# micromouse.net
KiCad netlist of a schematic drawn in EAGLE
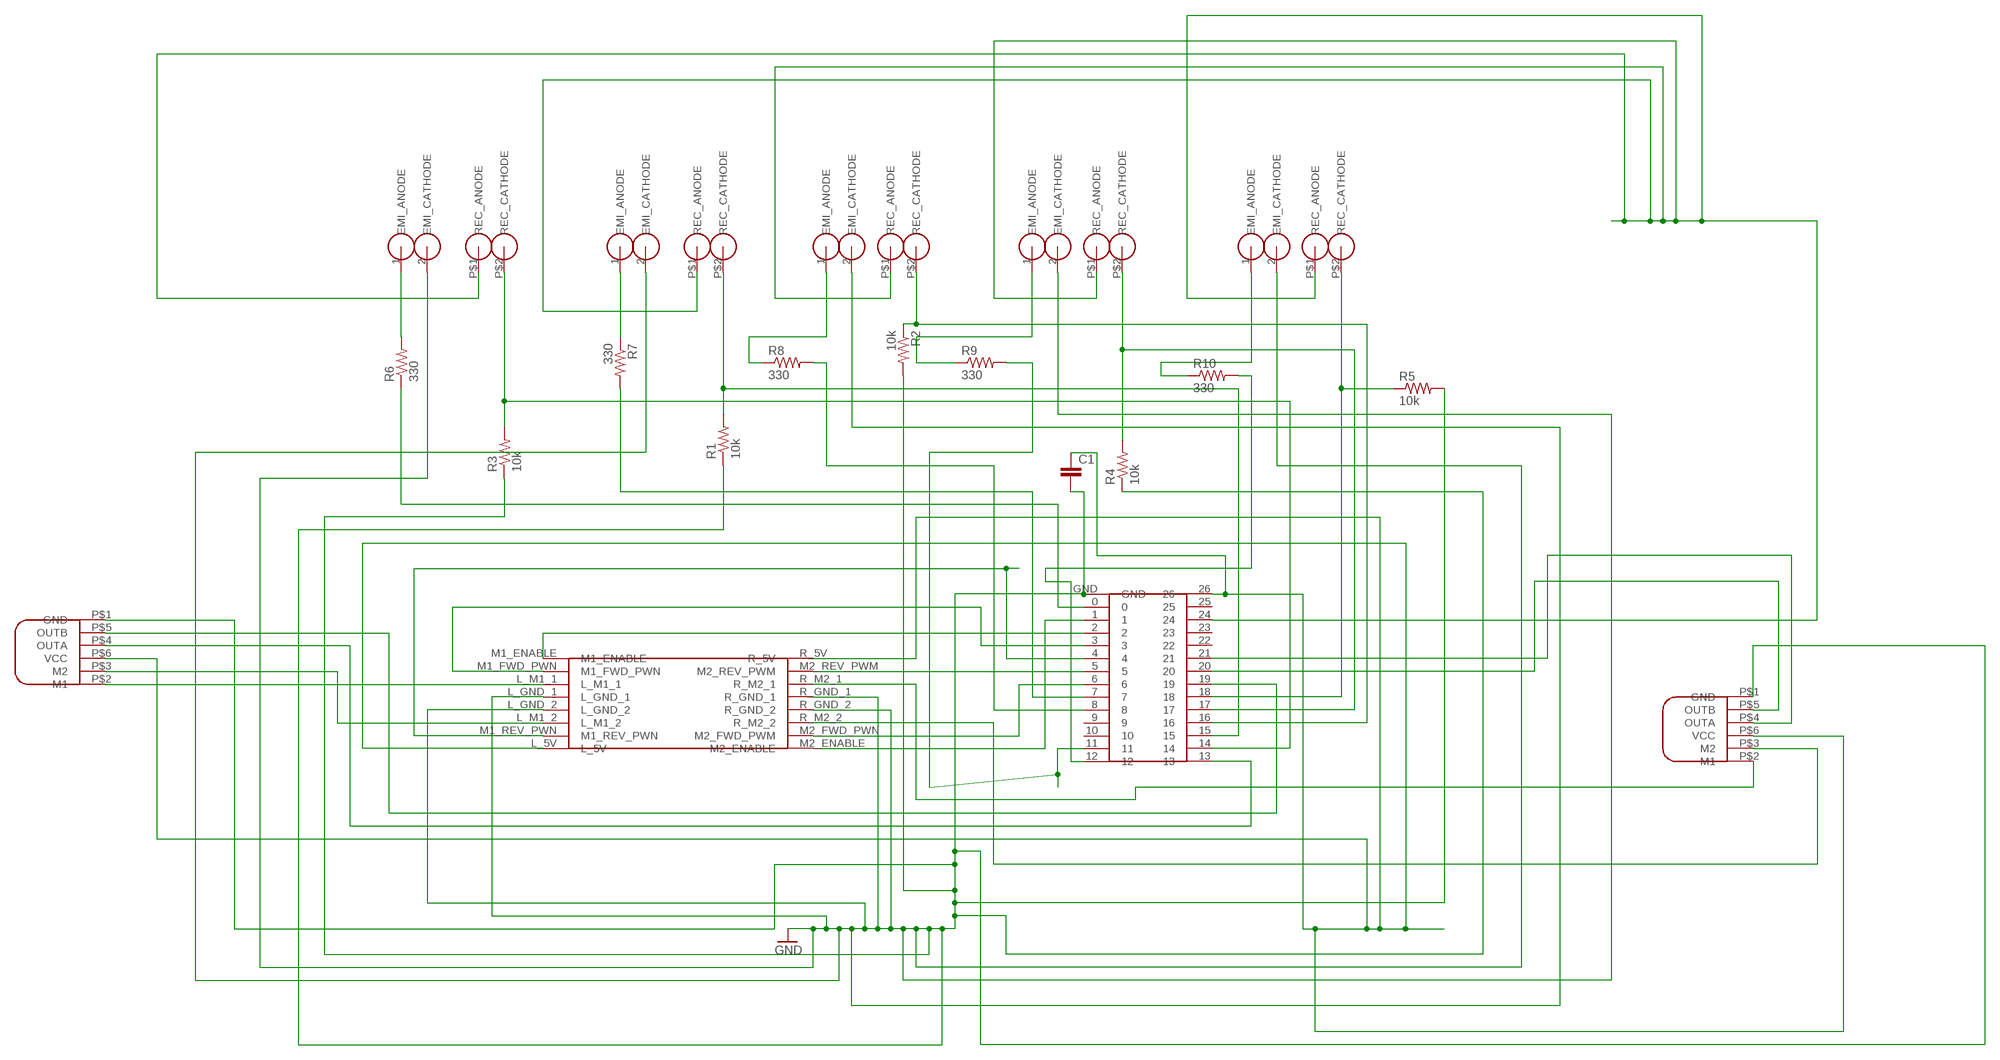
[diagram p0: schematic, sheet 1]

(export (version "E")
  (design (tool "Eeschema 10.0.6"))
  (components
    (comp (ref "C1")
      (value "C2,5-3")
      (footprint "eagle-import:C2.5-3")
      (libsource (lib "eagle-import") (part "C2,5-3"))
    )
    (comp (ref "R1")
      (value "10k")
      (footprint "eagle-import:0204_5")
      (libsource (lib "eagle-import") (part "R-US_0204/5"))
    )
    (comp (ref "R2")
      (value "10k")
      (footprint "eagle-import:0204_5")
      (libsource (lib "eagle-import") (part "R-US_0204/5"))
    )
    (comp (ref "R3")
      (value "10k")
      (footprint "eagle-import:0204_5")
      (libsource (lib "eagle-import") (part "R-US_0204/5"))
    )
    (comp (ref "R4")
      (value "10k")
      (footprint "eagle-import:0204_5")
      (libsource (lib "eagle-import") (part "R-US_0204/5"))
    )
    (comp (ref "R5")
      (value "10k")
      (footprint "eagle-import:0204_5")
      (libsource (lib "eagle-import") (part "R-US_0204/5"))
    )
    (comp (ref "R6")
      (value "330")
      (footprint "eagle-import:0204_5")
      (libsource (lib "eagle-import") (part "R-US_0204/5"))
    )
    (comp (ref "R7")
      (value "330")
      (footprint "eagle-import:0204_5")
      (libsource (lib "eagle-import") (part "R-US_0204/5"))
    )
    (comp (ref "R8")
      (value "330")
      (footprint "eagle-import:0204_5")
      (libsource (lib "eagle-import") (part "R-US_0204/5"))
    )
    (comp (ref "R9")
      (value "330")
      (footprint "eagle-import:0204_5")
      (libsource (lib "eagle-import") (part "R-US_0204/5"))
    )
    (comp (ref "R10")
      (value "330")
      (footprint "eagle-import:0204_5")
      (libsource (lib "eagle-import") (part "R-US_0204/5"))
    )
    (comp (ref "U$1")
      (value "TEENSY3.2")
      (footprint "eagle-import:TEENSY3.2")
      (libsource (lib "eagle-import") (part "TEENSY3.2"))
    )
    (comp (ref "U$2")
      (value "MOTOR_DRIVER")
      (footprint "eagle-import:MOTOR_DRIVER")
      (libsource (lib "eagle-import") (part "MOTOR_DRIVER"))
    )
    (comp (ref "U$3")
      (value "IR_RECIEVER")
      (footprint "eagle-import:IR_RECIEVER")
      (libsource (lib "eagle-import") (part "IR_RECIEVER"))
    )
    (comp (ref "U$4")
      (value "IR_RECIEVER")
      (footprint "eagle-import:IR_RECIEVER")
      (libsource (lib "eagle-import") (part "IR_RECIEVER"))
    )
    (comp (ref "U$5")
      (value "IR_RECIEVER")
      (footprint "eagle-import:IR_RECIEVER")
      (libsource (lib "eagle-import") (part "IR_RECIEVER"))
    )
    (comp (ref "U$6")
      (value "IR_RECIEVER")
      (footprint "eagle-import:IR_RECIEVER")
      (libsource (lib "eagle-import") (part "IR_RECIEVER"))
    )
    (comp (ref "U$7")
      (value "IR_RECIEVER")
      (footprint "eagle-import:IR_RECIEVER")
      (libsource (lib "eagle-import") (part "IR_RECIEVER"))
    )
    (comp (ref "U$8")
      (value "IR_EMITTER")
      (footprint "eagle-import:IR_EMITTER")
      (libsource (lib "eagle-import") (part "IR_EMITTER"))
    )
    (comp (ref "U$9")
      (value "IR_EMITTER")
      (footprint "eagle-import:IR_EMITTER")
      (libsource (lib "eagle-import") (part "IR_EMITTER"))
    )
    (comp (ref "U$10")
      (value "IR_EMITTER")
      (footprint "eagle-import:IR_EMITTER")
      (libsource (lib "eagle-import") (part "IR_EMITTER"))
    )
    (comp (ref "U$11")
      (value "IR_EMITTER")
      (footprint "eagle-import:IR_EMITTER")
      (libsource (lib "eagle-import") (part "IR_EMITTER"))
    )
    (comp (ref "U$12")
      (value "IR_EMITTER")
      (footprint "eagle-import:IR_EMITTER")
      (libsource (lib "eagle-import") (part "IR_EMITTER"))
    )
    (comp (ref "U$13")
      (value "MOTOR_ENCODER")
      (footprint "eagle-import:MOTOR_ENCODER")
      (libsource (lib "eagle-import") (part "MOTOR_ENCODER"))
    )
    (comp (ref "U$14")
      (value "MOTOR_ENCODER")
      (footprint "eagle-import:MOTOR_ENCODER")
      (libsource (lib "eagle-import") (part "MOTOR_ENCODER"))
    )
  )
  (nets
    (net (code "1") (name "GND") (class "Default")
      (node (ref "C1") (pin "2") (pinfunction "2_2") (pintype "passive"))
      (node (ref "R1") (pin "1") (pinfunction "1_1") (pintype "passive"))
      (node (ref "R2") (pin "2") (pinfunction "2_2") (pintype "passive"))
      (node (ref "R3") (pin "1") (pinfunction "1_1") (pintype "passive"))
      (node (ref "R4") (pin "1") (pinfunction "1_1") (pintype "passive"))
      (node (ref "R5") (pin "2") (pinfunction "2_2") (pintype "passive"))
      (node (ref "U$1") (pin "GND") (pinfunction "GND_GND") (pintype "bidirectional"))
      (node (ref "U$10") (pin "2") (pinfunction "EMI_CATHODE_2") (pintype "bidirectional"))
      (node (ref "U$11") (pin "2") (pinfunction "EMI_CATHODE_2") (pintype "bidirectional"))
      (node (ref "U$12") (pin "2") (pinfunction "EMI_CATHODE_2") (pintype "bidirectional"))
      (node (ref "U$13") (pin "P$1") (pinfunction "GND_P$1") (pintype "bidirectional"))
      (node (ref "U$14") (pin "P$1") (pinfunction "GND_P$1") (pintype "bidirectional"))
      (node (ref "U$2") (pin "L_GND_1") (pinfunction "L_GND_1_L_GND_1") (pintype "bidirectional"))
      (node (ref "U$2") (pin "L_GND_2") (pinfunction "L_GND_2_L_GND_2") (pintype "bidirectional"))
      (node (ref "U$2") (pin "R_GND_1") (pinfunction "R_GND_1_R_GND_1") (pintype "bidirectional"))
      (node (ref "U$2") (pin "R_GND_2") (pinfunction "R_GND_2_R_GND_2") (pintype "bidirectional"))
      (node (ref "U$8") (pin "2") (pinfunction "EMI_CATHODE_2") (pintype "bidirectional"))
      (node (ref "U$9") (pin "2") (pinfunction "EMI_CATHODE_2") (pintype "bidirectional"))
    )
    (net (code "2") (name "Net-(R6-Pad1)") (class "Default")
      (node (ref "R6") (pin "1") (pinfunction "1_1") (pintype "passive"))
      (node (ref "U$1") (pin "0") (pinfunction "0_0") (pintype "bidirectional"))
    )
    (net (code "3") (name "Net-(R7-Pad2)") (class "Default")
      (node (ref "R7") (pin "2") (pinfunction "2_2") (pintype "passive"))
      (node (ref "U$1") (pin "7") (pinfunction "7_7") (pintype "bidirectional"))
    )
    (net (code "4") (name "Net-(R8-Pad2)") (class "Default")
      (node (ref "R8") (pin "2") (pinfunction "2_2") (pintype "passive"))
      (node (ref "U$1") (pin "8") (pinfunction "8_8") (pintype "bidirectional"))
    )
    (net (code "5") (name "Net-(R9-Pad2)") (class "Default")
      (node (ref "R9") (pin "2") (pinfunction "2_2") (pintype "passive"))
      (node (ref "U$1") (pin "11") (pinfunction "11_11") (pintype "bidirectional"))
    )
    (net (code "6") (name "Net-(R10-Pad2)") (class "Default")
      (node (ref "R10") (pin "2") (pinfunction "2_2") (pintype "passive"))
      (node (ref "U$1") (pin "12") (pinfunction "12_12") (pintype "bidirectional"))
    )
    (net (code "7") (name "Net-(U$1-Pad1)") (class "Default")
      (node (ref "U$1") (pin "1") (pinfunction "1_1") (pintype "bidirectional"))
      (node (ref "U$2") (pin "M2_ENABLE") (pinfunction "M2_ENABLE_M2_ENABLE") (pintype "bidirectional"))
    )
    (net (code "8") (name "Net-(U$1-Pad2)") (class "Default")
      (node (ref "U$1") (pin "2") (pinfunction "2_2") (pintype "bidirectional"))
      (node (ref "U$2") (pin "M1_ENABLE") (pinfunction "M1_ENABLE_M1_ENABLE") (pintype "bidirectional"))
    )
    (net (code "9") (name "Net-(U$1-Pad3)") (class "Default")
      (node (ref "U$1") (pin "3") (pinfunction "3_3") (pintype "bidirectional"))
      (node (ref "U$2") (pin "M1_FWD_PWN") (pinfunction "M1_FWD_PWN_M1_FWD_PWN") (pintype "bidirectional"))
    )
    (net (code "10") (name "Net-(U$1-Pad4)") (class "Default")
      (node (ref "U$1") (pin "4") (pinfunction "4_4") (pintype "bidirectional"))
      (node (ref "U$2") (pin "M1_REV_PWN") (pinfunction "M1_REV_PWN_M1_REV_PWN") (pintype "bidirectional"))
    )
    (net (code "11") (name "Net-(U$1-Pad5)") (class "Default")
      (node (ref "U$1") (pin "5") (pinfunction "5_5") (pintype "bidirectional"))
      (node (ref "U$2") (pin "M2_REV_PWM") (pinfunction "M2_REV_PWM_M2_REV_PWM") (pintype "bidirectional"))
    )
    (net (code "12") (name "Net-(U$2-M2_FWD_PWM)") (class "Default")
      (node (ref "U$1") (pin "6") (pinfunction "6_6") (pintype "bidirectional"))
      (node (ref "U$2") (pin "M2_FWD_PWN") (pinfunction "M2_FWD_PWM_M2_FWD_PWN") (pintype "bidirectional"))
    )
    (net (code "13") (name "Net-(U$3-REC_ANODE)") (class "Default")
      (node (ref "U$1") (pin "24") (pinfunction "24_24") (pintype "bidirectional"))
      (node (ref "U$3") (pin "P$1") (pinfunction "REC_ANODE_P$1") (pintype "bidirectional"))
      (node (ref "U$4") (pin "P$1") (pinfunction "REC_ANODE_P$1") (pintype "bidirectional"))
      (node (ref "U$5") (pin "P$1") (pinfunction "REC_ANODE_P$1") (pintype "bidirectional"))
      (node (ref "U$6") (pin "P$1") (pinfunction "REC_ANODE_P$1") (pintype "bidirectional"))
      (node (ref "U$7") (pin "P$1") (pinfunction "REC_ANODE_P$1") (pintype "bidirectional"))
    )
    (net (code "14") (name "Net-(U$3-REC_CATHODE)") (class "Default")
      (node (ref "R3") (pin "2") (pinfunction "2_2") (pintype "passive"))
      (node (ref "U$1") (pin "14") (pinfunction "14_14") (pintype "bidirectional"))
      (node (ref "U$3") (pin "P$2") (pinfunction "REC_CATHODE_P$2") (pintype "bidirectional"))
    )
    (net (code "15") (name "Net-(U$4-REC_CATHODE)") (class "Default")
      (node (ref "R1") (pin "2") (pinfunction "2_2") (pintype "passive"))
      (node (ref "U$1") (pin "15") (pinfunction "15_15") (pintype "bidirectional"))
      (node (ref "U$4") (pin "P$2") (pinfunction "REC_CATHODE_P$2") (pintype "bidirectional"))
    )
    (net (code "16") (name "Net-(U$5-REC_CATHODE)") (class "Default")
      (node (ref "R2") (pin "1") (pinfunction "1_1") (pintype "passive"))
      (node (ref "U$1") (pin "16") (pinfunction "16_16") (pintype "bidirectional"))
      (node (ref "U$5") (pin "P$2") (pinfunction "REC_CATHODE_P$2") (pintype "bidirectional"))
    )
    (net (code "17") (name "Net-(U$6-REC_CATHODE)") (class "Default")
      (node (ref "R4") (pin "2") (pinfunction "2_2") (pintype "passive"))
      (node (ref "U$1") (pin "17") (pinfunction "17_17") (pintype "bidirectional"))
      (node (ref "U$6") (pin "P$2") (pinfunction "REC_CATHODE_P$2") (pintype "bidirectional"))
    )
    (net (code "18") (name "Net-(U$7-REC_CATHODE)") (class "Default")
      (node (ref "R5") (pin "1") (pinfunction "1_1") (pintype "passive"))
      (node (ref "U$1") (pin "18") (pinfunction "18_18") (pintype "bidirectional"))
      (node (ref "U$7") (pin "P$2") (pinfunction "REC_CATHODE_P$2") (pintype "bidirectional"))
    )
    (net (code "19") (name "Net-(U$8-EMI_ANODE)") (class "Default")
      (node (ref "R6") (pin "2") (pinfunction "2_2") (pintype "passive"))
      (node (ref "U$8") (pin "1") (pinfunction "EMI_ANODE_1") (pintype "bidirectional"))
    )
    (net (code "20") (name "Net-(U$9-EMI_ANODE)") (class "Default")
      (node (ref "R7") (pin "1") (pinfunction "1_1") (pintype "passive"))
      (node (ref "U$9") (pin "1") (pinfunction "EMI_ANODE_1") (pintype "bidirectional"))
    )
    (net (code "21") (name "Net-(U$10-EMI_ANODE)") (class "Default")
      (node (ref "R8") (pin "1") (pinfunction "1_1") (pintype "passive"))
      (node (ref "U$10") (pin "1") (pinfunction "EMI_ANODE_1") (pintype "bidirectional"))
    )
    (net (code "22") (name "Net-(U$11-EMI_ANODE)") (class "Default")
      (node (ref "R9") (pin "1") (pinfunction "1_1") (pintype "passive"))
      (node (ref "U$11") (pin "1") (pinfunction "EMI_ANODE_1") (pintype "bidirectional"))
    )
    (net (code "23") (name "Net-(U$12-EMI_ANODE)") (class "Default")
      (node (ref "R10") (pin "1") (pinfunction "1_1") (pintype "passive"))
      (node (ref "U$12") (pin "1") (pinfunction "EMI_ANODE_1") (pintype "bidirectional"))
    )
    (net (code "24") (name "Net-(U$13-M1)") (class "Default")
      (node (ref "U$13") (pin "P$2") (pinfunction "M1_P$2") (pintype "bidirectional"))
      (node (ref "U$2") (pin "L_M1_1") (pinfunction "L_M1_1_L_M1_1") (pintype "bidirectional"))
    )
    (net (code "25") (name "Net-(U$13-M2)") (class "Default")
      (node (ref "U$13") (pin "P$3") (pinfunction "M2_P$3") (pintype "bidirectional"))
      (node (ref "U$2") (pin "L_M1_2") (pinfunction "L_M1_2_L_M1_2") (pintype "bidirectional"))
    )
    (net (code "26") (name "Net-(U$13-OUTA)") (class "Default")
      (node (ref "U$1") (pin "13") (pinfunction "13_13") (pintype "bidirectional"))
      (node (ref "U$13") (pin "P$4") (pinfunction "OUTA_P$4") (pintype "bidirectional"))
    )
    (net (code "27") (name "Net-(U$13-OUTB)") (class "Default")
      (node (ref "U$1") (pin "19") (pinfunction "19_19") (pintype "bidirectional"))
      (node (ref "U$13") (pin "P$5") (pinfunction "OUTB_P$5") (pintype "bidirectional"))
    )
    (net (code "28") (name "Net-(U$13-VCC)") (class "Default")
      (node (ref "C1") (pin "1") (pinfunction "1_1") (pintype "passive"))
      (node (ref "U$1") (pin "26") (pinfunction "26_26") (pintype "bidirectional"))
      (node (ref "U$13") (pin "P$6") (pinfunction "VCC_P$6") (pintype "bidirectional"))
      (node (ref "U$14") (pin "P$6") (pinfunction "VCC_P$6") (pintype "bidirectional"))
      (node (ref "U$2") (pin "L_5V") (pinfunction "L_5V_L_5V") (pintype "bidirectional"))
      (node (ref "U$2") (pin "R_5V") (pinfunction "R_5V_R_5V") (pintype "bidirectional"))
    )
    (net (code "29") (name "Net-(U$14-M1)") (class "Default")
      (node (ref "U$14") (pin "P$2") (pinfunction "M1_P$2") (pintype "bidirectional"))
      (node (ref "U$2") (pin "R_M2_1") (pinfunction "R_M2_1_R_M2_1") (pintype "bidirectional"))
    )
    (net (code "30") (name "Net-(U$14-M2)") (class "Default")
      (node (ref "U$14") (pin "P$3") (pinfunction "M2_P$3") (pintype "bidirectional"))
      (node (ref "U$2") (pin "R_M2_2") (pinfunction "R_M2_2_R_M2_2") (pintype "bidirectional"))
    )
    (net (code "31") (name "Net-(U$14-OUTA)") (class "Default")
      (node (ref "U$1") (pin "21") (pinfunction "21_21") (pintype "bidirectional"))
      (node (ref "U$14") (pin "P$4") (pinfunction "OUTA_P$4") (pintype "bidirectional"))
    )
    (net (code "32") (name "Net-(U$14-OUTB)") (class "Default")
      (node (ref "U$1") (pin "20") (pinfunction "20_20") (pintype "bidirectional"))
      (node (ref "U$14") (pin "P$5") (pinfunction "OUTB_P$5") (pintype "bidirectional"))
    )
    (net (code "33") (name "unconnected-(U$1-Pad9)") (class "Default")
      (node (ref "U$1") (pin "9") (pinfunction "9_9") (pintype "bidirectional"))
    )
    (net (code "34") (name "unconnected-(U$1-Pad10)") (class "Default")
      (node (ref "U$1") (pin "10") (pinfunction "10_10") (pintype "bidirectional"))
    )
    (net (code "35") (name "unconnected-(U$1-Pad22)") (class "Default")
      (node (ref "U$1") (pin "22") (pinfunction "22_22") (pintype "bidirectional"))
    )
    (net (code "36") (name "unconnected-(U$1-Pad23)") (class "Default")
      (node (ref "U$1") (pin "23") (pinfunction "23_23") (pintype "bidirectional"))
    )
    (net (code "37") (name "unconnected-(U$1-Pad25)") (class "Default")
      (node (ref "U$1") (pin "25") (pinfunction "25_25") (pintype "bidirectional"))
    )
  )
)
